# frc_operator_interface.net
KiCad netlist of a schematic drawn in EAGLE
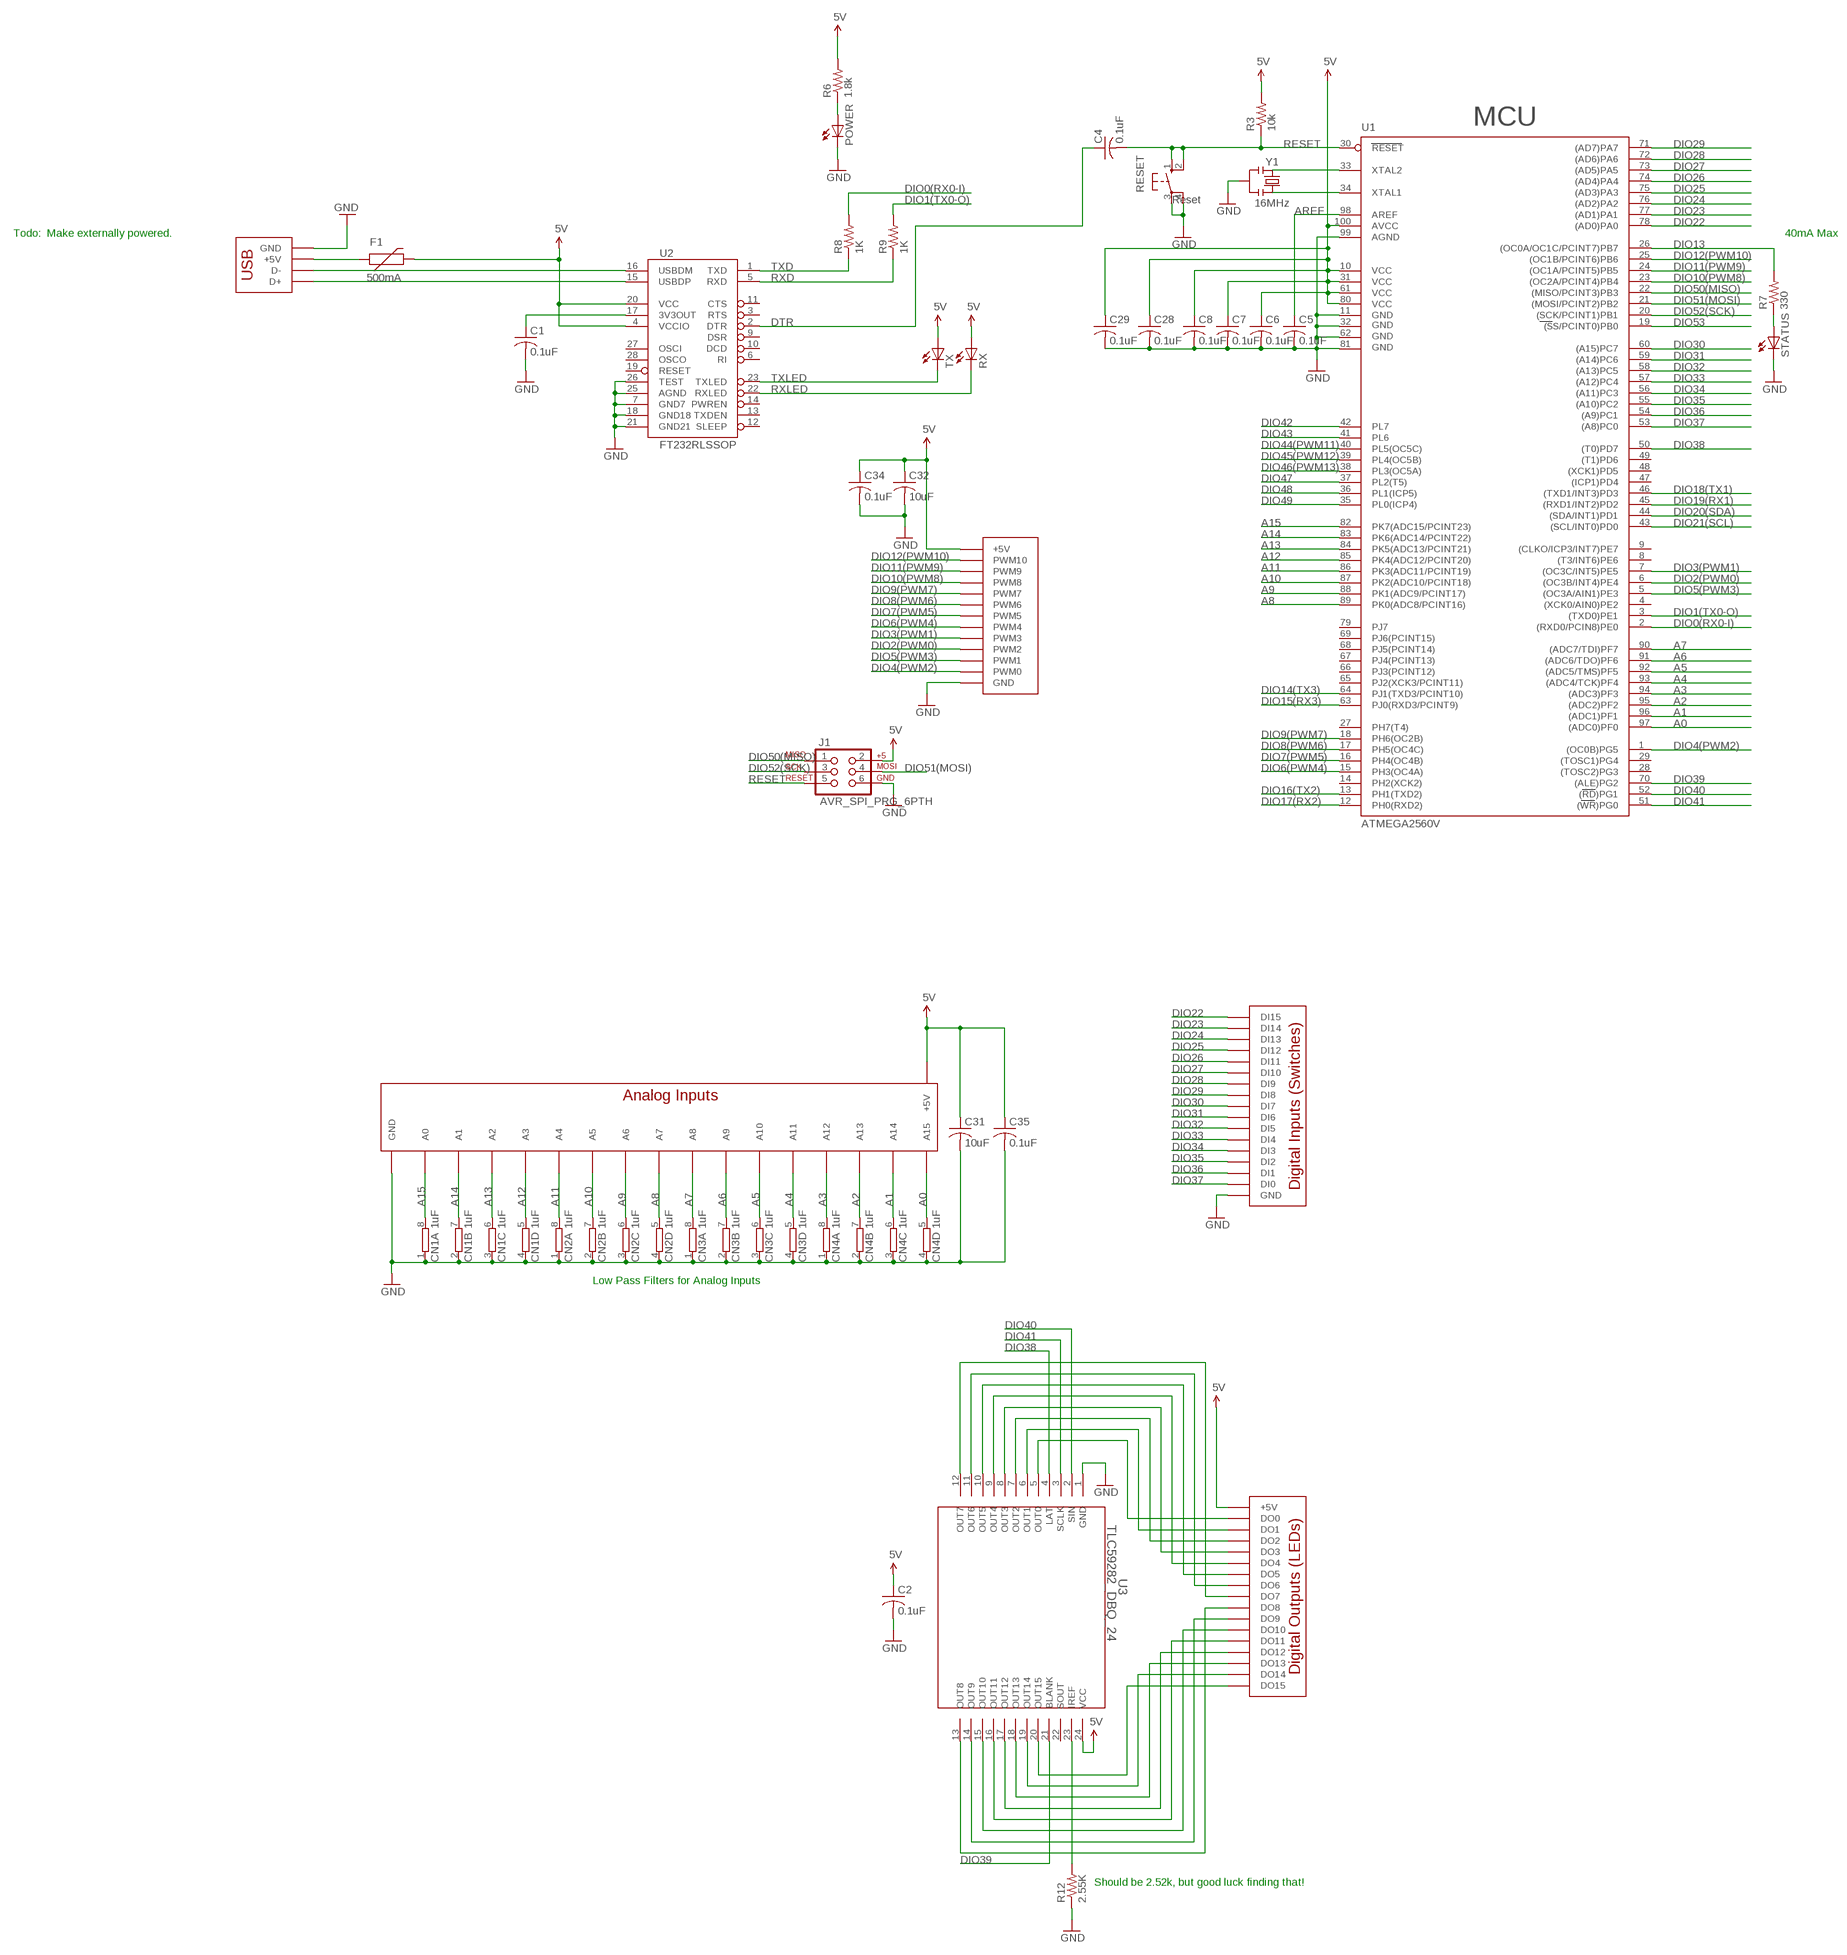
[diagram p0: schematic, sheet 1]

(export (version "E")
  (design (tool "Eeschema 10.0.6"))
  (components
    (comp (ref "C1")
      (value "0.1uF")
      (footprint "eagle-import:C1206")
      (libsource (lib "eagle-import") (part "C-USC1206"))
    )
    (comp (ref "C2")
      (value "0.1uF")
      (footprint "eagle-import:C1206")
      (libsource (lib "eagle-import") (part "C-USC1206"))
    )
    (comp (ref "C4")
      (value "0.1uF")
      (footprint "eagle-import:C1206")
      (libsource (lib "eagle-import") (part "C-USC1206"))
    )
    (comp (ref "C5")
      (value "0.1uF")
      (footprint "eagle-import:C1206")
      (libsource (lib "eagle-import") (part "C-USC1206"))
    )
    (comp (ref "C6")
      (value "0.1uF")
      (footprint "eagle-import:C1206")
      (libsource (lib "eagle-import") (part "C-USC1206"))
    )
    (comp (ref "C7")
      (value "0.1uF")
      (footprint "eagle-import:C1206")
      (libsource (lib "eagle-import") (part "C-USC1206"))
    )
    (comp (ref "C8")
      (value "0.1uF")
      (footprint "eagle-import:C1206")
      (libsource (lib "eagle-import") (part "C-USC1206"))
    )
    (comp (ref "C28")
      (value "0.1uF")
      (footprint "eagle-import:C1206")
      (libsource (lib "eagle-import") (part "C-USC1206"))
    )
    (comp (ref "C29")
      (value "0.1uF")
      (footprint "eagle-import:C1206")
      (libsource (lib "eagle-import") (part "C-USC1206"))
    )
    (comp (ref "C31")
      (value "10uF")
      (footprint "eagle-import:C1206")
      (libsource (lib "eagle-import") (part "C-USC1206"))
    )
    (comp (ref "C32")
      (value "10uF")
      (footprint "eagle-import:C1206")
      (libsource (lib "eagle-import") (part "C-USC1206"))
    )
    (comp (ref "C34")
      (value "0.1uF")
      (footprint "eagle-import:C1206")
      (libsource (lib "eagle-import") (part "C-USC1206"))
    )
    (comp (ref "C35")
      (value "0.1uF")
      (footprint "eagle-import:C1206")
      (libsource (lib "eagle-import") (part "C-USC1206"))
    )
    (comp (ref "CN1")
      (value "1uF")
      (footprint "eagle-import:EXB38V")
      (libsource (lib "eagle-import") (part "4R-NEXB38V"))
    )
    (comp (ref "CN2")
      (value "1uF")
      (footprint "eagle-import:EXB38V")
      (libsource (lib "eagle-import") (part "4R-NEXB38V"))
    )
    (comp (ref "CN3")
      (value "1uF")
      (footprint "eagle-import:EXB38V")
      (libsource (lib "eagle-import") (part "4R-NEXB38V"))
    )
    (comp (ref "CN4")
      (value "1uF")
      (footprint "eagle-import:EXB38V")
      (libsource (lib "eagle-import") (part "4R-NEXB38V"))
    )
    (comp (ref "F1")
      (value "500mA")
      (footprint "eagle-import:PTC-1206")
      (libsource (lib "eagle-import") (part "PTCSMD"))
    )
    (comp (ref "J1")
      (value "AVR_SPI_PRG_6PTH")
      (footprint "eagle-import:2X3")
      (libsource (lib "eagle-import") (part "AVR_SPI_PRG_6PTH"))
    )
    (comp (ref "J2")
      (value "ANALOGHEADER")
      (footprint "eagle-import:ANALOGHEADER")
      (libsource (lib "eagle-import") (part "ANALOGHEADER"))
    )
    (comp (ref "J3")
      (value "DIGITALIN")
      (footprint "eagle-import:DIGITALIN")
      (libsource (lib "eagle-import") (part "DIGITALIN"))
    )
    (comp (ref "J4")
      (value "DIGITALOUTPUTS")
      (footprint "eagle-import:DIGITALOUT")
      (libsource (lib "eagle-import") (part "DIGITALOUTPUTS"))
    )
    (comp (ref "J5")
      (value "PWMHEADER")
      (footprint "eagle-import:PWMHEADER")
      (libsource (lib "eagle-import") (part "PWMHEADER"))
    )
    (comp (ref "J6")
      (value "UE27BC54130-USB")
      (footprint "eagle-import:UE27BC54130-USB")
      (libsource (lib "eagle-import") (part "UE27BC54130-USB"))
    )
    (comp (ref "POWER")
      (value "LED3MM")
      (footprint "eagle-import:LED3MM")
      (libsource (lib "eagle-import") (part "LED3MM"))
    )
    (comp (ref "R3")
      (value "10k")
      (footprint "eagle-import:M1206")
      (libsource (lib "eagle-import") (part "R-US_M1206"))
    )
    (comp (ref "R6")
      (value "1.8k")
      (footprint "eagle-import:M1206")
      (libsource (lib "eagle-import") (part "R-US_M1206"))
    )
    (comp (ref "R7")
      (value "330")
      (footprint "eagle-import:M1206")
      (libsource (lib "eagle-import") (part "R-US_M1206"))
    )
    (comp (ref "R8")
      (value "1K")
      (footprint "eagle-import:M1206")
      (libsource (lib "eagle-import") (part "R-US_M1206"))
    )
    (comp (ref "R9")
      (value "1K")
      (footprint "eagle-import:M1206")
      (libsource (lib "eagle-import") (part "R-US_M1206"))
    )
    (comp (ref "R12")
      (value "2.55K")
      (footprint "eagle-import:M1206")
      (libsource (lib "eagle-import") (part "R-US_M1206"))
    )
    (comp (ref "RESET")
      (value "10-XX")
      (footprint "eagle-import:B3F-10XX")
      (fields (field (name "MPN") "B3F-1000"))
      (libsource (lib "eagle-import") (part "10-XX"))
    )
    (comp (ref "RX")
      (value "LED3MM")
      (footprint "eagle-import:LED3MM")
      (libsource (lib "eagle-import") (part "LED3MM"))
    )
    (comp (ref "STATUS")
      (value "LED3MM")
      (footprint "eagle-import:LED3MM")
      (libsource (lib "eagle-import") (part "LED3MM"))
    )
    (comp (ref "TX")
      (value "LED3MM")
      (footprint "eagle-import:LED3MM")
      (libsource (lib "eagle-import") (part "LED3MM"))
    )
    (comp (ref "U1")
      (value "ATMEGA2560AU")
      (footprint "eagle-import:TQFP100")
      (libsource (lib "eagle-import") (part "ATMEGA2560AU"))
    )
    (comp (ref "U2")
      (value "FT232RLSSOP")
      (footprint "eagle-import:SSOP28DB")
      (libsource (lib "eagle-import") (part "FT232RLSSOP"))
    )
    (comp (ref "U3")
      (value "TLC59282_DBQ_24")
      (footprint "eagle-import:DBQ24")
      (fields
        (field (name "GENERIC_PART_NUMBER") "TLC59282")
        (field (name "MANUFACTURER") "Texas Instruments")
        (field (name "MANUFACTURER_PART_NUMBER") "tlc59282_dbq_24")
      )
      (libsource (lib "eagle-import") (part "TLC59282_DBQ_24"))
    )
    (comp (ref "Y1")
      (value "RESONATORSMD")
      (footprint "eagle-import:RESONATOR-SMD")
      (libsource (lib "eagle-import") (part "RESONATORSMD"))
    )
  )
  (nets
    (net (code "1") (name "/A0") (class "Default")
      (node (ref "CN4") (pin "5") (pinfunction "2_5") (pintype "passive"))
      (node (ref "J2") (pin "15") (pinfunction "A15_15") (pintype "bidirectional"))
      (node (ref "U1") (pin "97") (pinfunction "(ADC0)PF0_97") (pintype "bidirectional"))
    )
    (net (code "2") (name "/A1") (class "Default")
      (node (ref "CN4") (pin "6") (pinfunction "2_6") (pintype "passive"))
      (node (ref "J2") (pin "14") (pinfunction "A14_14") (pintype "bidirectional"))
      (node (ref "U1") (pin "96") (pinfunction "(ADC1)PF1_96") (pintype "bidirectional"))
    )
    (net (code "3") (name "/A2") (class "Default")
      (node (ref "CN4") (pin "7") (pinfunction "2_7") (pintype "passive"))
      (node (ref "J2") (pin "13") (pinfunction "A13_13") (pintype "bidirectional"))
      (node (ref "U1") (pin "95") (pinfunction "(ADC2)PF2_95") (pintype "bidirectional"))
    )
    (net (code "4") (name "/A3") (class "Default")
      (node (ref "CN4") (pin "8") (pinfunction "2_8") (pintype "passive"))
      (node (ref "J2") (pin "12") (pinfunction "A12_12") (pintype "bidirectional"))
      (node (ref "U1") (pin "94") (pinfunction "(ADC3)PF3_94") (pintype "bidirectional"))
    )
    (net (code "5") (name "/A4") (class "Default")
      (node (ref "CN3") (pin "5") (pinfunction "2_5") (pintype "passive"))
      (node (ref "J2") (pin "11") (pinfunction "A11_11") (pintype "bidirectional"))
      (node (ref "U1") (pin "93") (pinfunction "(ADC4/TCK)PF4_93") (pintype "bidirectional"))
    )
    (net (code "6") (name "/A5") (class "Default")
      (node (ref "CN3") (pin "6") (pinfunction "2_6") (pintype "passive"))
      (node (ref "J2") (pin "10") (pinfunction "A10_10") (pintype "bidirectional"))
      (node (ref "U1") (pin "92") (pinfunction "(ADC5/TMS)PF5_92") (pintype "bidirectional"))
    )
    (net (code "7") (name "/A6") (class "Default")
      (node (ref "CN3") (pin "7") (pinfunction "2_7") (pintype "passive"))
      (node (ref "J2") (pin "9") (pinfunction "A9_9") (pintype "bidirectional"))
      (node (ref "U1") (pin "91") (pinfunction "(ADC6/TDO)PF6_91") (pintype "bidirectional"))
    )
    (net (code "8") (name "/A7") (class "Default")
      (node (ref "CN3") (pin "8") (pinfunction "2_8") (pintype "passive"))
      (node (ref "J2") (pin "8") (pinfunction "A8_8") (pintype "bidirectional"))
      (node (ref "U1") (pin "90") (pinfunction "(ADC7/TDI)PF7_90") (pintype "bidirectional"))
    )
    (net (code "9") (name "/A8") (class "Default")
      (node (ref "CN2") (pin "5") (pinfunction "2_5") (pintype "passive"))
      (node (ref "J2") (pin "7") (pinfunction "A7_7") (pintype "bidirectional"))
      (node (ref "U1") (pin "89") (pinfunction "PK0(ADC8/PCINT16)_89") (pintype "bidirectional"))
    )
    (net (code "10") (name "/A9") (class "Default")
      (node (ref "CN2") (pin "6") (pinfunction "2_6") (pintype "passive"))
      (node (ref "J2") (pin "6") (pinfunction "A6_6") (pintype "bidirectional"))
      (node (ref "U1") (pin "88") (pinfunction "PK1(ADC9/PCINT17)_88") (pintype "bidirectional"))
    )
    (net (code "11") (name "/A10") (class "Default")
      (node (ref "CN2") (pin "7") (pinfunction "2_7") (pintype "passive"))
      (node (ref "J2") (pin "5") (pinfunction "A5_5") (pintype "bidirectional"))
      (node (ref "U1") (pin "87") (pinfunction "PK2(ADC10/PCINT18)_87") (pintype "bidirectional"))
    )
    (net (code "12") (name "/A11") (class "Default")
      (node (ref "CN2") (pin "8") (pinfunction "2_8") (pintype "passive"))
      (node (ref "J2") (pin "4") (pinfunction "A4_4") (pintype "bidirectional"))
      (node (ref "U1") (pin "86") (pinfunction "PK3(ADC11/PCINT19)_86") (pintype "bidirectional"))
    )
    (net (code "13") (name "/A12") (class "Default")
      (node (ref "CN1") (pin "5") (pinfunction "2_5") (pintype "passive"))
      (node (ref "J2") (pin "3") (pinfunction "A3_3") (pintype "bidirectional"))
      (node (ref "U1") (pin "85") (pinfunction "PK4(ADC12/PCINT20)_85") (pintype "bidirectional"))
    )
    (net (code "14") (name "/A13") (class "Default")
      (node (ref "CN1") (pin "6") (pinfunction "2_6") (pintype "passive"))
      (node (ref "J2") (pin "2") (pinfunction "A2_2") (pintype "bidirectional"))
      (node (ref "U1") (pin "84") (pinfunction "PK5(ADC13/PCINT21)_84") (pintype "bidirectional"))
    )
    (net (code "15") (name "/A14") (class "Default")
      (node (ref "CN1") (pin "7") (pinfunction "2_7") (pintype "passive"))
      (node (ref "J2") (pin "1") (pinfunction "A1_1") (pintype "bidirectional"))
      (node (ref "U1") (pin "83") (pinfunction "PK6(ADC14/PCINT22)_83") (pintype "bidirectional"))
    )
    (net (code "16") (name "/A15") (class "Default")
      (node (ref "CN1") (pin "8") (pinfunction "2_8") (pintype "passive"))
      (node (ref "J2") (pin "0") (pinfunction "A0_0") (pintype "bidirectional"))
      (node (ref "U1") (pin "82") (pinfunction "PK7(ADC15/PCINT23)_82") (pintype "bidirectional"))
    )
    (net (code "17") (name "/AREF") (class "Default")
      (node (ref "C5") (pin "1") (pinfunction "1_1") (pintype "passive"))
      (node (ref "U1") (pin "98") (pinfunction "AREF_98") (pintype "bidirectional"))
    )
    (net (code "18") (name "/DIO0(RX0-I)") (class "Default")
      (node (ref "R8") (pin "2") (pinfunction "2_2") (pintype "passive"))
      (node (ref "U1") (pin "2") (pinfunction "(RXD0/PCIN8)PE0_2") (pintype "bidirectional"))
    )
    (net (code "19") (name "/DIO1(TX0-O)") (class "Default")
      (node (ref "R9") (pin "2") (pinfunction "2_2") (pintype "passive"))
      (node (ref "U1") (pin "3") (pinfunction "(TXD0)PE1_3") (pintype "bidirectional"))
    )
    (net (code "20") (name "/DIO2(PWM0)") (class "Default")
      (node (ref "J5") (pin "2") (pinfunction "PWM2_2") (pintype "output"))
      (node (ref "U1") (pin "6") (pinfunction "(OC3B/INT4)PE4_6") (pintype "bidirectional"))
    )
    (net (code "21") (name "/DIO3(PWM1)") (class "Default")
      (node (ref "J5") (pin "3") (pinfunction "PWM3_3") (pintype "output"))
      (node (ref "U1") (pin "7") (pinfunction "(OC3C/INT5)PE5_7") (pintype "bidirectional"))
    )
    (net (code "22") (name "/DIO4(PWM2)") (class "Default")
      (node (ref "J5") (pin "0") (pinfunction "PWM0_0") (pintype "output"))
      (node (ref "U1") (pin "1") (pinfunction "(OC0B)PG5_1") (pintype "bidirectional"))
    )
    (net (code "23") (name "/DIO5(PWM3)") (class "Default")
      (node (ref "J5") (pin "1") (pinfunction "PWM1_1") (pintype "output"))
      (node (ref "U1") (pin "5") (pinfunction "(OC3A/AIN1)PE3_5") (pintype "bidirectional"))
    )
    (net (code "24") (name "/DIO6(PWM4)") (class "Default")
      (node (ref "J5") (pin "4") (pinfunction "PWM4_4") (pintype "output"))
      (node (ref "U1") (pin "15") (pinfunction "PH3(OC4A)_15") (pintype "bidirectional"))
    )
    (net (code "25") (name "/DIO7(PWM5)") (class "Default")
      (node (ref "J5") (pin "5") (pinfunction "PWM5_5") (pintype "output"))
      (node (ref "U1") (pin "16") (pinfunction "PH4(OC4B)_16") (pintype "bidirectional"))
    )
    (net (code "26") (name "/DIO8(PWM6)") (class "Default")
      (node (ref "J5") (pin "6") (pinfunction "PWM6_6") (pintype "output"))
      (node (ref "U1") (pin "17") (pinfunction "PH5(OC4C)_17") (pintype "bidirectional"))
    )
    (net (code "27") (name "/DIO9(PWM7)") (class "Default")
      (node (ref "J5") (pin "7") (pinfunction "PWM7_7") (pintype "output"))
      (node (ref "U1") (pin "18") (pinfunction "PH6(OC2B)_18") (pintype "bidirectional"))
    )
    (net (code "28") (name "/DIO10(PWM8)") (class "Default")
      (node (ref "J5") (pin "8") (pinfunction "PWM8_8") (pintype "output"))
      (node (ref "U1") (pin "23") (pinfunction "(OC2A/PCINT4)PB4_23") (pintype "bidirectional"))
    )
    (net (code "29") (name "/DIO11(PWM9)") (class "Default")
      (node (ref "J5") (pin "9") (pinfunction "PWM9_9") (pintype "output"))
      (node (ref "U1") (pin "24") (pinfunction "(OC1A/PCINT5)PB5_24") (pintype "bidirectional"))
    )
    (net (code "30") (name "/DIO12(PWM10)") (class "Default")
      (node (ref "J5") (pin "10") (pinfunction "PWM10_10") (pintype "output"))
      (node (ref "U1") (pin "25") (pinfunction "(OC1B/PCINT6)PB6_25") (pintype "bidirectional"))
    )
    (net (code "31") (name "/DIO13") (class "Default")
      (node (ref "R7") (pin "2") (pinfunction "2_2") (pintype "passive"))
      (node (ref "U1") (pin "26") (pinfunction "(OC0A/OC1C/PCINT7)PB7_26") (pintype "bidirectional"))
    )
    (net (code "32") (name "/DIO14(TX3)") (class "Default")
      (node (ref "U1") (pin "64") (pinfunction "PJ1(TXD3/PCINT10)_64") (pintype "bidirectional"))
    )
    (net (code "33") (name "/DIO15(RX3)") (class "Default")
      (node (ref "U1") (pin "63") (pinfunction "PJ0(RXD3/PCINT9)_63") (pintype "bidirectional"))
    )
    (net (code "34") (name "/DIO16(TX2)") (class "Default")
      (node (ref "U1") (pin "13") (pinfunction "PH1(TXD2)_13") (pintype "bidirectional"))
    )
    (net (code "35") (name "/DIO17(RX2)") (class "Default")
      (node (ref "U1") (pin "12") (pinfunction "PH0(RXD2)_12") (pintype "bidirectional"))
    )
    (net (code "36") (name "/DIO18(TX1)") (class "Default")
      (node (ref "U1") (pin "46") (pinfunction "(TXD1/INT3)PD3_46") (pintype "bidirectional"))
    )
    (net (code "37") (name "/DIO19(RX1)") (class "Default")
      (node (ref "U1") (pin "45") (pinfunction "(RXD1/INT2)PD2_45") (pintype "bidirectional"))
    )
    (net (code "38") (name "/DIO20(SDA)") (class "Default")
      (node (ref "U1") (pin "44") (pinfunction "(SDA/INT1)PD1_44") (pintype "bidirectional"))
    )
    (net (code "39") (name "/DIO21(SCL)") (class "Default")
      (node (ref "U1") (pin "43") (pinfunction "(SCL/INT0)PD0_43") (pintype "bidirectional"))
    )
    (net (code "40") (name "/DIO22") (class "Default")
      (node (ref "J3") (pin "DI15") (pinfunction "DI15_DI15") (pintype "bidirectional"))
      (node (ref "U1") (pin "78") (pinfunction "(AD0)PA0_78") (pintype "bidirectional"))
    )
    (net (code "41") (name "/DIO23") (class "Default")
      (node (ref "J3") (pin "DI14") (pinfunction "DI14_DI14") (pintype "bidirectional"))
      (node (ref "U1") (pin "77") (pinfunction "(AD1)PA1_77") (pintype "bidirectional"))
    )
    (net (code "42") (name "/DIO24") (class "Default")
      (node (ref "J3") (pin "DI13") (pinfunction "DI13_DI13") (pintype "bidirectional"))
      (node (ref "U1") (pin "76") (pinfunction "(AD2)PA2_76") (pintype "bidirectional"))
    )
    (net (code "43") (name "/DIO25") (class "Default")
      (node (ref "J3") (pin "DI12") (pinfunction "DI12_DI12") (pintype "bidirectional"))
      (node (ref "U1") (pin "75") (pinfunction "(AD3)PA3_75") (pintype "bidirectional"))
    )
    (net (code "44") (name "/DIO26") (class "Default")
      (node (ref "J3") (pin "DI11") (pinfunction "DI11_DI11") (pintype "bidirectional"))
      (node (ref "U1") (pin "74") (pinfunction "(AD4)PA4_74") (pintype "bidirectional"))
    )
    (net (code "45") (name "/DIO27") (class "Default")
      (node (ref "J3") (pin "DI10") (pinfunction "DI10_DI10") (pintype "bidirectional"))
      (node (ref "U1") (pin "73") (pinfunction "(AD5)PA5_73") (pintype "bidirectional"))
    )
    (net (code "46") (name "/DIO28") (class "Default")
      (node (ref "J3") (pin "DI9") (pinfunction "DI9_DI9") (pintype "bidirectional"))
      (node (ref "U1") (pin "72") (pinfunction "(AD6)PA6_72") (pintype "bidirectional"))
    )
    (net (code "47") (name "/DIO29") (class "Default")
      (node (ref "J3") (pin "DI8") (pinfunction "DI8_DI8") (pintype "bidirectional"))
      (node (ref "U1") (pin "71") (pinfunction "(AD7)PA7_71") (pintype "bidirectional"))
    )
    (net (code "48") (name "/DIO30") (class "Default")
      (node (ref "J3") (pin "DI7") (pinfunction "DI7_DI7") (pintype "bidirectional"))
      (node (ref "U1") (pin "60") (pinfunction "(A15)PC7_60") (pintype "bidirectional"))
    )
    (net (code "49") (name "/DIO31") (class "Default")
      (node (ref "J3") (pin "DI6") (pinfunction "DI6_DI6") (pintype "bidirectional"))
      (node (ref "U1") (pin "59") (pinfunction "(A14)PC6_59") (pintype "bidirectional"))
    )
    (net (code "50") (name "/DIO32") (class "Default")
      (node (ref "J3") (pin "DI5") (pinfunction "DI5_DI5") (pintype "bidirectional"))
      (node (ref "U1") (pin "58") (pinfunction "(A13)PC5_58") (pintype "bidirectional"))
    )
    (net (code "51") (name "/DIO33") (class "Default")
      (node (ref "J3") (pin "DI4") (pinfunction "DI4_DI4") (pintype "bidirectional"))
      (node (ref "U1") (pin "57") (pinfunction "(A12)PC4_57") (pintype "bidirectional"))
    )
    (net (code "52") (name "/DIO34") (class "Default")
      (node (ref "J3") (pin "DI3") (pinfunction "DI3_DI3") (pintype "bidirectional"))
      (node (ref "U1") (pin "56") (pinfunction "(A11)PC3_56") (pintype "bidirectional"))
    )
    (net (code "53") (name "/DIO35") (class "Default")
      (node (ref "J3") (pin "DI2") (pinfunction "DI2_DI2") (pintype "bidirectional"))
      (node (ref "U1") (pin "55") (pinfunction "(A10)PC2_55") (pintype "bidirectional"))
    )
    (net (code "54") (name "/DIO36") (class "Default")
      (node (ref "J3") (pin "DI1") (pinfunction "DI1_DI1") (pintype "bidirectional"))
      (node (ref "U1") (pin "54") (pinfunction "(A9)PC1_54") (pintype "bidirectional"))
    )
    (net (code "55") (name "/DIO37") (class "Default")
      (node (ref "J3") (pin "DI0") (pinfunction "DI0_DI0") (pintype "bidirectional"))
      (node (ref "U1") (pin "53") (pinfunction "(A8)PC0_53") (pintype "bidirectional"))
    )
    (net (code "56") (name "/DIO38") (class "Default")
      (node (ref "U1") (pin "50") (pinfunction "(T0)PD7_50") (pintype "bidirectional"))
      (node (ref "U3") (pin "4") (pinfunction "LAT_4") (pintype "input"))
    )
    (net (code "57") (name "/DIO39") (class "Default")
      (node (ref "U1") (pin "70") (pinfunction "(ALE)PG2_70") (pintype "bidirectional"))
      (node (ref "U3") (pin "21") (pinfunction "BLANK_21") (pintype "input"))
    )
    (net (code "58") (name "/DIO40") (class "Default")
      (node (ref "U1") (pin "52") (pinfunction "(RD)PG1_52") (pintype "bidirectional"))
      (node (ref "U3") (pin "2") (pinfunction "SIN_2") (pintype "input"))
    )
    (net (code "59") (name "/DIO41") (class "Default")
      (node (ref "U1") (pin "51") (pinfunction "(WR)PG0_51") (pintype "bidirectional"))
      (node (ref "U3") (pin "3") (pinfunction "SCLK_3") (pintype "input"))
    )
    (net (code "60") (name "/DIO42") (class "Default")
      (node (ref "U1") (pin "42") (pinfunction "PL7_42") (pintype "bidirectional"))
    )
    (net (code "61") (name "/DIO43") (class "Default")
      (node (ref "U1") (pin "41") (pinfunction "PL6_41") (pintype "bidirectional"))
    )
    (net (code "62") (name "/DIO44(PWM11)") (class "Default")
      (node (ref "U1") (pin "40") (pinfunction "PL5(OC5C)_40") (pintype "bidirectional"))
    )
    (net (code "63") (name "/DIO45(PWM12)") (class "Default")
      (node (ref "U1") (pin "39") (pinfunction "PL4(OC5B)_39") (pintype "bidirectional"))
    )
    (net (code "64") (name "/DIO46(PWM13)") (class "Default")
      (node (ref "U1") (pin "38") (pinfunction "PL3(OC5A)_38") (pintype "bidirectional"))
    )
    (net (code "65") (name "/DIO47") (class "Default")
      (node (ref "U1") (pin "37") (pinfunction "PL2(T5)_37") (pintype "bidirectional"))
    )
    (net (code "66") (name "/DIO48") (class "Default")
      (node (ref "U1") (pin "36") (pinfunction "PL1(ICP5)_36") (pintype "bidirectional"))
    )
    (net (code "67") (name "/DIO49") (class "Default")
      (node (ref "U1") (pin "35") (pinfunction "PL0(ICP4)_35") (pintype "bidirectional"))
    )
    (net (code "68") (name "/DIO50(MISO)") (class "Default")
      (node (ref "J1") (pin "1") (pinfunction "1_1") (pintype "passive"))
      (node (ref "U1") (pin "22") (pinfunction "(MISO/PCINT3)PB3_22") (pintype "bidirectional"))
    )
    (net (code "69") (name "/DIO51(MOSI)") (class "Default")
      (node (ref "J1") (pin "4") (pinfunction "4_4") (pintype "passive"))
      (node (ref "U1") (pin "21") (pinfunction "(MOSI/PCINT2)PB2_21") (pintype "bidirectional"))
    )
    (net (code "70") (name "/DIO52(SCK)") (class "Default")
      (node (ref "J1") (pin "3") (pinfunction "3_3") (pintype "passive"))
      (node (ref "U1") (pin "20") (pinfunction "(SCK/PCINT1)PB1_20") (pintype "bidirectional"))
    )
    (net (code "71") (name "/DIO53") (class "Default")
      (node (ref "U1") (pin "19") (pinfunction "(SS/PCINT0)PB0_19") (pintype "bidirectional"))
    )
    (net (code "72") (name "/DTR") (class "Default")
      (node (ref "C4") (pin "1") (pinfunction "1_1") (pintype "passive"))
      (node (ref "U2") (pin "2") (pinfunction "DTR_2") (pintype "output"))
    )
    (net (code "73") (name "/RESET") (class "Default")
      (node (ref "C4") (pin "2") (pinfunction "2_2") (pintype "passive"))
      (node (ref "J1") (pin "5") (pinfunction "5_5") (pintype "passive"))
      (node (ref "R3") (pin "1") (pinfunction "1_1") (pintype "passive"))
      (node (ref "RESET") (pin "1") (pinfunction "S_1") (pintype "passive"))
      (node (ref "RESET") (pin "2") (pinfunction "S1_2") (pintype "passive"))
      (node (ref "U1") (pin "30") (pinfunction "RESET_30") (pintype "input"))
    )
    (net (code "74") (name "/RXD") (class "Default")
      (node (ref "R9") (pin "1") (pinfunction "1_1") (pintype "passive"))
      (node (ref "U2") (pin "5") (pinfunction "RXD_5") (pintype "input"))
    )
    (net (code "75") (name "/RXLED") (class "Default")
      (node (ref "RX") (pin "K") (pinfunction "C_K") (pintype "passive"))
      (node (ref "U2") (pin "22") (pinfunction "RXLED_22") (pintype "input"))
    )
    (net (code "76") (name "/TXD") (class "Default")
      (node (ref "R8") (pin "1") (pinfunction "1_1") (pintype "passive"))
      (node (ref "U2") (pin "1") (pinfunction "TXD_1") (pintype "output"))
    )
    (net (code "77") (name "/TXLED") (class "Default")
      (node (ref "TX") (pin "K") (pinfunction "C_K") (pintype "passive"))
      (node (ref "U2") (pin "23") (pinfunction "TXLED_23") (pintype "input"))
    )
    (net (code "78") (name "5V") (class "Default")
      (node (ref "C2") (pin "1") (pinfunction "1_1") (pintype "passive"))
      (node (ref "C28") (pin "1") (pinfunction "1_1") (pintype "passive"))
      (node (ref "C29") (pin "1") (pinfunction "1_1") (pintype "passive"))
      (node (ref "C31") (pin "1") (pinfunction "1_1") (pintype "passive"))
      (node (ref "C32") (pin "1") (pinfunction "1_1") (pintype "passive"))
      (node (ref "C34") (pin "1") (pinfunction "1_1") (pintype "passive"))
      (node (ref "C35") (pin "1") (pinfunction "1_1") (pintype "passive"))
      (node (ref "C6") (pin "1") (pinfunction "1_1") (pintype "passive"))
      (node (ref "C7") (pin "1") (pinfunction "1_1") (pintype "passive"))
      (node (ref "C8") (pin "1") (pinfunction "1_1") (pintype "passive"))
      (node (ref "F1") (pin "2") (pinfunction "2_2") (pintype "bidirectional"))
      (node (ref "J1") (pin "2") (pinfunction "2_2") (pintype "passive"))
      (node (ref "J2") (pin "+5V@0") (pinfunction "+5V_+5V@0") (pintype "bidirectional"))
      (node (ref "J2") (pin "+5V@1") (pinfunction "+5V_+5V@1") (pintype "bidirectional"))
      (node (ref "J2") (pin "+5V@10") (pinfunction "+5V_+5V@10") (pintype "bidirectional"))
      (node (ref "J2") (pin "+5V@11") (pinfunction "+5V_+5V@11") (pintype "bidirectional"))
      (node (ref "J2") (pin "+5V@12") (pinfunction "+5V_+5V@12") (pintype "bidirectional"))
      (node (ref "J2") (pin "+5V@13") (pinfunction "+5V_+5V@13") (pintype "bidirectional"))
      (node (ref "J2") (pin "+5V@14") (pinfunction "+5V_+5V@14") (pintype "bidirectional"))
      (node (ref "J2") (pin "+5V@15") (pinfunction "+5V_+5V@15") (pintype "bidirectional"))
      (node (ref "J2") (pin "+5V@2") (pinfunction "+5V_+5V@2") (pintype "bidirectional"))
      (node (ref "J2") (pin "+5V@3") (pinfunction "+5V_+5V@3") (pintype "bidirectional"))
      (node (ref "J2") (pin "+5V@4") (pinfunction "+5V_+5V@4") (pintype "bidirectional"))
      (node (ref "J2") (pin "+5V@5") (pinfunction "+5V_+5V@5") (pintype "bidirectional"))
      (node (ref "J2") (pin "+5V@6") (pinfunction "+5V_+5V@6") (pintype "bidirectional"))
      (node (ref "J2") (pin "+5V@7") (pinfunction "+5V_+5V@7") (pintype "bidirectional"))
      (node (ref "J2") (pin "+5V@8") (pinfunction "+5V_+5V@8") (pintype "bidirectional"))
      (node (ref "J2") (pin "+5V@9") (pinfunction "+5V_+5V@9") (pintype "bidirectional"))
      (node (ref "J4") (pin "+5V@0") (pinfunction "+5V_+5V@0") (pintype "power_in"))
      (node (ref "J4") (pin "+5V@1") (pinfunction "+5V_+5V@1") (pintype "power_in"))
      (node (ref "J4") (pin "+5V@10") (pinfunction "+5V_+5V@10") (pintype "power_in"))
      (node (ref "J4") (pin "+5V@11") (pinfunction "+5V_+5V@11") (pintype "power_in"))
      (node (ref "J4") (pin "+5V@12") (pinfunction "+5V_+5V@12") (pintype "power_in"))
      (node (ref "J4") (pin "+5V@13") (pinfunction "+5V_+5V@13") (pintype "power_in"))
      (node (ref "J4") (pin "+5V@14") (pinfunction "+5V_+5V@14") (pintype "power_in"))
      (node (ref "J4") (pin "+5V@15") (pinfunction "+5V_+5V@15") (pintype "power_in"))
      (node (ref "J4") (pin "+5V@2") (pinfunction "+5V_+5V@2") (pintype "power_in"))
      (node (ref "J4") (pin "+5V@3") (pinfunction "+5V_+5V@3") (pintype "power_in"))
      (node (ref "J4") (pin "+5V@4") (pinfunction "+5V_+5V@4") (pintype "power_in"))
      (node (ref "J4") (pin "+5V@5") (pinfunction "+5V_+5V@5") (pintype "power_in"))
      (node (ref "J4") (pin "+5V@6") (pinfunction "+5V_+5V@6") (pintype "power_in"))
      (node (ref "J4") (pin "+5V@7") (pinfunction "+5V_+5V@7") (pintype "power_in"))
      (node (ref "J4") (pin "+5V@8") (pinfunction "+5V_+5V@8") (pintype "power_in"))
      (node (ref "J4") (pin "+5V@9") (pinfunction "+5V_+5V@9") (pintype "power_in"))
      (node (ref "J5") (pin "+5V@10") (pinfunction "+5V_+5V@10") (pintype "power_in"))
      (node (ref "J5") (pin "+5V@11") (pinfunction "+5V_+5V@11") (pintype "power_in"))
      (node (ref "J5") (pin "+5V@12") (pinfunction "+5V_+5V@12") (pintype "power_in"))
      (node (ref "J5") (pin "+5V@13") (pinfunction "+5V_+5V@13") (pintype "power_in"))
      (node (ref "J5") (pin "+5V@3") (pinfunction "+5V_+5V@3") (pintype "power_in"))
      (node (ref "J5") (pin "+5V@4") (pinfunction "+5V_+5V@4") (pintype "power_in"))
      (node (ref "J5") (pin "+5V@5") (pinfunction "+5V_+5V@5") (pintype "power_in"))
      (node (ref "J5") (pin "+5V@6") (pinfunction "+5V_+5V@6") (pintype "power_in"))
      (node (ref "J5") (pin "+5V@7") (pinfunction "+5V_+5V@7") (pintype "power_in"))
      (node (ref "J5") (pin "+5V@8") (pinfunction "+5V_+5V@8") (pintype "power_in"))
      (node (ref "J5") (pin "+5V@9") (pinfunction "+5V_+5V@9") (pintype "power_in"))
      (node (ref "R3") (pin "2") (pinfunction "2_2") (pintype "passive"))
      (node (ref "R6") (pin "2") (pinfunction "2_2") (pintype "passive"))
      (node (ref "RX") (pin "A") (pinfunction "A_A") (pintype "passive"))
      (node (ref "TX") (pin "A") (pinfunction "A_A") (pintype "passive"))
      (node (ref "U1") (pin "10") (pinfunction "VCC_10") (pintype "power_in"))
      (node (ref "U1") (pin "100") (pinfunction "AVCC_100") (pintype "power_in"))
      (node (ref "U1") (pin "31") (pinfunction "VCC1_31") (pintype "power_in"))
      (node (ref "U1") (pin "61") (pinfunction "VCC2_61") (pintype "power_in"))
      (node (ref "U1") (pin "80") (pinfunction "VCC3_80") (pintype "power_in"))
      (node (ref "U2") (pin "20") (pinfunction "VCC_20") (pintype "power_in"))
      (node (ref "U2") (pin "4") (pinfunction "VCCIO_4") (pintype "power_in"))
      (node (ref "U3") (pin "24") (pinfunction "VCC_24") (pintype "power_in"))
    )
    (net (code "79") (name "GND") (class "Default")
      (node (ref "C1") (pin "2") (pinfunction "2_2") (pintype "passive"))
      (node (ref "C2") (pin "2") (pinfunction "2_2") (pintype "passive"))
      (node (ref "C28") (pin "2") (pinfunction "2_2") (pintype "passive"))
      (node (ref "C29") (pin "2") (pinfunction "2_2") (pintype "passive"))
      (node (ref "C31") (pin "2") (pinfunction "2_2") (pintype "passive"))
      (node (ref "C32") (pin "2") (pinfunction "2_2") (pintype "passive"))
      (node (ref "C34") (pin "2") (pinfunction "2_2") (pintype "passive"))
      (node (ref "C35") (pin "2") (pinfunction "2_2") (pintype "passive"))
      (node (ref "C5") (pin "2") (pinfunction "2_2") (pintype "passive"))
      (node (ref "C6") (pin "2") (pinfunction "2_2") (pintype "passive"))
      (node (ref "C7") (pin "2") (pinfunction "2_2") (pintype "passive"))
      (node (ref "C8") (pin "2") (pinfunction "2_2") (pintype "passive"))
      (node (ref "CN1") (pin "1") (pinfunction "1_1") (pintype "passive"))
      (node (ref "CN1") (pin "2") (pinfunction "1_2") (pintype "passive"))
      (node (ref "CN1") (pin "3") (pinfunction "1_3") (pintype "passive"))
      (node (ref "CN1") (pin "4") (pinfunction "1_4") (pintype "passive"))
      (node (ref "CN2") (pin "1") (pinfunction "1_1") (pintype "passive"))
      (node (ref "CN2") (pin "2") (pinfunction "1_2") (pintype "passive"))
      (node (ref "CN2") (pin "3") (pinfunction "1_3") (pintype "passive"))
      (node (ref "CN2") (pin "4") (pinfunction "1_4") (pintype "passive"))
      (node (ref "CN3") (pin "1") (pinfunction "1_1") (pintype "passive"))
      (node (ref "CN3") (pin "2") (pinfunction "1_2") (pintype "passive"))
      (node (ref "CN3") (pin "3") (pinfunction "1_3") (pintype "passive"))
      (node (ref "CN3") (pin "4") (pinfunction "1_4") (pintype "passive"))
      (node (ref "CN4") (pin "1") (pinfunction "1_1") (pintype "passive"))
      (node (ref "CN4") (pin "2") (pinfunction "1_2") (pintype "passive"))
      (node (ref "CN4") (pin "3") (pinfunction "1_3") (pintype "passive"))
      (node (ref "CN4") (pin "4") (pinfunction "1_4") (pintype "passive"))
      (node (ref "J1") (pin "6") (pinfunction "6_6") (pintype "passive"))
      (node (ref "J2") (pin "GND@0") (pinfunction "GND_GND@0") (pintype "bidirectional"))
      (node (ref "J2") (pin "GND@1") (pinfunction "GND_GND@1") (pintype "bidirectional"))
      (node (ref "J2") (pin "GND@10") (pinfunction "GND_GND@10") (pintype "bidirectional"))
      (node (ref "J2") (pin "GND@11") (pinfunction "GND_GND@11") (pintype "bidirectional"))
      (node (ref "J2") (pin "GND@12") (pinfunction "GND_GND@12") (pintype "bidirectional"))
      (node (ref "J2") (pin "GND@13") (pinfunction "GND_GND@13") (pintype "bidirectional"))
      (node (ref "J2") (pin "GND@14") (pinfunction "GND_GND@14") (pintype "bidirectional"))
      (node (ref "J2") (pin "GND@15") (pinfunction "GND_GND@15") (pintype "bidirectional"))
      (node (ref "J2") (pin "GND@2") (pinfunction "GND_GND@2") (pintype "bidirectional"))
      (node (ref "J2") (pin "GND@3") (pinfunction "GND_GND@3") (pintype "bidirectional"))
      (node (ref "J2") (pin "GND@4") (pinfunction "GND_GND@4") (pintype "bidirectional"))
      (node (ref "J2") (pin "GND@5") (pinfunction "GND_GND@5") (pintype "bidirectional"))
      (node (ref "J2") (pin "GND@6") (pinfunction "GND_GND@6") (pintype "bidirectional"))
      (node (ref "J2") (pin "GND@7") (pinfunction "GND_GND@7") (pintype "bidirectional"))
      (node (ref "J2") (pin "GND@8") (pinfunction "GND_GND@8") (pintype "bidirectional"))
      (node (ref "J2") (pin "GND@9") (pinfunction "GND_GND@9") (pintype "bidirectional"))
      (node (ref "J3") (pin "GND@0") (pinfunction "GND_GND@0") (pintype "power_in"))
      (node (ref "J3") (pin "GND@1") (pinfunction "GND_GND@1") (pintype "power_in"))
      (node (ref "J3") (pin "GND@10") (pinfunction "GND_GND@10") (pintype "power_in"))
      (node (ref "J3") (pin "GND@11") (pinfunction "GND_GND@11") (pintype "power_in"))
      (node (ref "J3") (pin "GND@12") (pinfunction "GND_GND@12") (pintype "power_in"))
      (node (ref "J3") (pin "GND@13") (pinfunction "GND_GND@13") (pintype "power_in"))
      (node (ref "J3") (pin "GND@14") (pinfunction "GND_GND@14") (pintype "power_in"))
      (node (ref "J3") (pin "GND@15") (pinfunction "GND_GND@15") (pintype "power_in"))
      (node (ref "J3") (pin "GND@2") (pinfunction "GND_GND@2") (pintype "power_in"))
      (node (ref "J3") (pin "GND@3") (pinfunction "GND_GND@3") (pintype "power_in"))
      (node (ref "J3") (pin "GND@4") (pinfunction "GND_GND@4") (pintype "power_in"))
      (node (ref "J3") (pin "GND@5") (pinfunction "GND_GND@5") (pintype "power_in"))
      (node (ref "J3") (pin "GND@6") (pinfunction "GND_GND@6") (pintype "power_in"))
      (node (ref "J3") (pin "GND@7") (pinfunction "GND_GND@7") (pintype "power_in"))
      (node (ref "J3") (pin "GND@8") (pinfunction "GND_GND@8") (pintype "power_in"))
      (node (ref "J3") (pin "GND@9") (pinfunction "GND_GND@9") (pintype "power_in"))
      (node (ref "J5") (pin "GND@10") (pinfunction "GND_GND@10") (pintype "power_in"))
      (node (ref "J5") (pin "GND@11") (pinfunction "GND_GND@11") (pintype "power_in"))
      (node (ref "J5") (pin "GND@12") (pinfunction "GND_GND@12") (pintype "power_in"))
      (node (ref "J5") (pin "GND@13") (pinfunction "GND_GND@13") (pintype "power_in"))
      (node (ref "J5") (pin "GND@3") (pinfunction "GND_GND@3") (pintype "power_in"))
      (node (ref "J5") (pin "GND@4") (pinfunction "GND_GND@4") (pintype "power_in"))
      (node (ref "J5") (pin "GND@5") (pinfunction "GND_GND@5") (pintype "power_in"))
      (node (ref "J5") (pin "GND@6") (pinfunction "GND_GND@6") (pintype "power_in"))
      (node (ref "J5") (pin "GND@7") (pinfunction "GND_GND@7") (pintype "power_in"))
      (node (ref "J5") (pin "GND@8") (pinfunction "GND_GND@8") (pintype "power_in"))
      (node (ref "J5") (pin "GND@9") (pinfunction "GND_GND@9") (pintype "power_in"))
      (node (ref "J6") (pin "GND@0") (pinfunction "GND_GND@0") (pintype "power_in"))
      (node (ref "J6") (pin "GND@1") (pinfunction "GND_GND@1") (pintype "power_in"))
      (node (ref "J6") (pin "GND@2") (pinfunction "GND_GND@2") (pintype "power_in"))
      (node (ref "POWER") (pin "K") (pinfunction "C_K") (pintype "passive"))
      (node (ref "R12") (pin "1") (pinfunction "1_1") (pintype "passive"))
      (node (ref "RESET") (pin "3") (pinfunction "P_3") (pintype "passive"))
      (node (ref "RESET") (pin "4") (pinfunction "P1_4") (pintype "passive"))
      (node (ref "STATUS") (pin "K") (pinfunction "C_K") (pintype "passive"))
      (node (ref "U1") (pin "11") (pinfunction "GND_11") (pintype "power_in"))
      (node (ref "U1") (pin "32") (pinfunction "GND1_32") (pintype "power_in"))
      (node (ref "U1") (pin "62") (pinfunction "GND2_62") (pintype "power_in"))
      (node (ref "U1") (pin "81") (pinfunction "GND3_81") (pintype "power_in"))
      (node (ref "U1") (pin "99") (pinfunction "AGND_99") (pintype "power_in"))
      (node (ref "U2") (pin "18") (pinfunction "GND18_18") (pintype "power_in"))
      (node (ref "U2") (pin "21") (pinfunction "GND21_21") (pintype "power_in"))
      (node (ref "U2") (pin "25") (pinfunction "AGND_25") (pintype "power_in"))
      (node (ref "U2") (pin "26") (pinfunction "TEST_26") (pintype "input"))
      (node (ref "U2") (pin "7") (pinfunction "GND7_7") (pintype "power_in"))
      (node (ref "U3") (pin "1") (pinfunction "GND_1") (pintype "power_in"))
      (node (ref "Y1") (pin "2") (pinfunction "2_2") (pintype "passive"))
    )
    (net (code "80") (name "Net-(F1-Pad1)") (class "Default")
      (node (ref "F1") (pin "1") (pinfunction "1_1") (pintype "bidirectional"))
      (node (ref "J6") (pin "+5V") (pinfunction "+5V_+5V") (pintype "power_in"))
    )
    (net (code "81") (name "Net-(J6-D+)") (class "Default")
      (node (ref "J6") (pin "+DATA") (pinfunction "D+_+DATA") (pintype "bidirectional"))
      (node (ref "U2") (pin "15") (pinfunction "USBDP_15") (pintype "bidirectional"))
    )
    (net (code "82") (name "Net-(J6-D-)") (class "Default")
      (node (ref "J6") (pin "-DATA") (pinfunction "D-_-DATA") (pintype "bidirectional"))
      (node (ref "U2") (pin "16") (pinfunction "USBDM_16") (pintype "bidirectional"))
    )
    (net (code "83") (name "Net-(POWER-PadA)") (class "Default")
      (node (ref "POWER") (pin "A") (pinfunction "A_A") (pintype "passive"))
      (node (ref "R6") (pin "1") (pinfunction "1_1") (pintype "passive"))
    )
    (net (code "84") (name "Net-(R7-Pad1)") (class "Default")
      (node (ref "R7") (pin "1") (pinfunction "1_1") (pintype "passive"))
      (node (ref "STATUS") (pin "A") (pinfunction "A_A") (pintype "passive"))
    )
    (net (code "85") (name "Net-(U1-XTAL1)") (class "Default")
      (node (ref "U1") (pin "34") (pinfunction "XTAL1_34") (pintype "input"))
      (node (ref "Y1") (pin "3") (pinfunction "3_3") (pintype "passive"))
    )
    (net (code "86") (name "Net-(U1-XTAL2)") (class "Default")
      (node (ref "U1") (pin "33") (pinfunction "XTAL2_33") (pintype "output"))
      (node (ref "Y1") (pin "1") (pinfunction "1_1") (pintype "passive"))
    )
    (net (code "87") (name "Net-(U2-3V3OUT)") (class "Default")
      (node (ref "C1") (pin "1") (pinfunction "1_1") (pintype "passive"))
      (node (ref "U2") (pin "17") (pinfunction "3V3OUT_17") (pintype "output"))
    )
    (net (code "88") (name "Net-(U3-IREF)") (class "Default")
      (node (ref "R12") (pin "2") (pinfunction "2_2") (pintype "passive"))
      (node (ref "U3") (pin "23") (pinfunction "IREF_23") (pintype "bidirectional"))
    )
    (net (code "89") (name "Net-(U3-OUT0)") (class "Default")
      (node (ref "J4") (pin "DO0") (pinfunction "DO0_DO0") (pintype "bidirectional"))
      (node (ref "U3") (pin "5") (pinfunction "OUT0_5") (pintype "output"))
    )
    (net (code "90") (name "Net-(U3-OUT1)") (class "Default")
      (node (ref "J4") (pin "DO1") (pinfunction "DO1_DO1") (pintype "bidirectional"))
      (node (ref "U3") (pin "6") (pinfunction "OUT1_6") (pintype "output"))
    )
    (net (code "91") (name "Net-(U3-OUT2)") (class "Default")
      (node (ref "J4") (pin "DO2") (pinfunction "DO2_DO2") (pintype "bidirectional"))
      (node (ref "U3") (pin "7") (pinfunction "OUT2_7") (pintype "output"))
    )
    (net (code "92") (name "Net-(U3-OUT3)") (class "Default")
      (node (ref "J4") (pin "DO3") (pinfunction "DO3_DO3") (pintype "bidirectional"))
      (node (ref "U3") (pin "8") (pinfunction "OUT3_8") (pintype "output"))
    )
    (net (code "93") (name "Net-(U3-OUT4)") (class "Default")
      (node (ref "J4") (pin "DO4") (pinfunction "DO4_DO4") (pintype "bidirectional"))
      (node (ref "U3") (pin "9") (pinfunction "OUT4_9") (pintype "output"))
    )
    (net (code "94") (name "Net-(U3-OUT5)") (class "Default")
      (node (ref "J4") (pin "DO5") (pinfunction "DO5_DO5") (pintype "bidirectional"))
      (node (ref "U3") (pin "10") (pinfunction "OUT5_10") (pintype "output"))
    )
    (net (code "95") (name "Net-(U3-OUT6)") (class "Default")
      (node (ref "J4") (pin "DO6") (pinfunction "DO6_DO6") (pintype "bidirectional"))
      (node (ref "U3") (pin "11") (pinfunction "OUT6_11") (pintype "output"))
    )
    (net (code "96") (name "Net-(U3-OUT7)") (class "Default")
      (node (ref "J4") (pin "DO7") (pinfunction "DO7_DO7") (pintype "bidirectional"))
      (node (ref "U3") (pin "12") (pinfunction "OUT7_12") (pintype "output"))
    )
    (net (code "97") (name "Net-(U3-OUT8)") (class "Default")
      (node (ref "J4") (pin "DO8") (pinfunction "DO8_DO8") (pintype "bidirectional"))
      (node (ref "U3") (pin "13") (pinfunction "OUT8_13") (pintype "output"))
    )
    (net (code "98") (name "Net-(U3-OUT9)") (class "Default")
      (node (ref "J4") (pin "DO9") (pinfunction "DO9_DO9") (pintype "bidirectional"))
      (node (ref "U3") (pin "14") (pinfunction "OUT9_14") (pintype "output"))
    )
    (net (code "99") (name "Net-(U3-OUT10)") (class "Default")
      (node (ref "J4") (pin "DO10") (pinfunction "DO10_DO10") (pintype "bidirectional"))
      (node (ref "U3") (pin "15") (pinfunction "OUT10_15") (pintype "output"))
    )
    (net (code "100") (name "Net-(U3-OUT11)") (class "Default")
      (node (ref "J4") (pin "DO11") (pinfunction "DO11_DO11") (pintype "bidirectional"))
      (node (ref "U3") (pin "16") (pinfunction "OUT11_16") (pintype "output"))
    )
    (net (code "101") (name "Net-(U3-OUT12)") (class "Default")
      (node (ref "J4") (pin "DO12") (pinfunction "DO12_DO12") (pintype "bidirectional"))
      (node (ref "U3") (pin "17") (pinfunction "OUT12_17") (pintype "output"))
    )
    (net (code "102") (name "Net-(U3-OUT13)") (class "Default")
      (node (ref "J4") (pin "DO13") (pinfunction "DO13_DO13") (pintype "bidirectional"))
      (node (ref "U3") (pin "18") (pinfunction "OUT13_18") (pintype "output"))
    )
    (net (code "103") (name "Net-(U3-OUT14)") (class "Default")
      (node (ref "J4") (pin "DO14") (pinfunction "DO14_DO14") (pintype "bidirectional"))
      (node (ref "U3") (pin "19") (pinfunction "OUT14_19") (pintype "output"))
    )
    (net (code "104") (name "Net-(U3-OUT15)") (class "Default")
      (node (ref "J4") (pin "DO15") (pinfunction "DO15_DO15") (pintype "bidirectional"))
      (node (ref "U3") (pin "20") (pinfunction "OUT15_20") (pintype "output"))
    )
    (net (code "105") (name "unconnected-(U1-(CLKO{slash}ICP3{slash}INT7)PE7-Pad9)") (class "Default")
      (node (ref "U1") (pin "9") (pinfunction "(CLKO/ICP3/INT7)PE7_9") (pintype "bidirectional"))
    )
    (net (code "106") (name "unconnected-(U1-(ICP1)PD4-Pad47)") (class "Default")
      (node (ref "U1") (pin "47") (pinfunction "(ICP1)PD4_47") (pintype "bidirectional"))
    )
    (net (code "107") (name "unconnected-(U1-(T1)PD6-Pad49)") (class "Default")
      (node (ref "U1") (pin "49") (pinfunction "(T1)PD6_49") (pintype "bidirectional"))
    )
    (net (code "108") (name "unconnected-(U1-(T3{slash}INT6)PE6-Pad8)") (class "Default")
      (node (ref "U1") (pin "8") (pinfunction "(T3/INT6)PE6_8") (pintype "bidirectional"))
    )
    (net (code "109") (name "unconnected-(U1-(TOSC1)PG4-Pad29)") (class "Default")
      (node (ref "U1") (pin "29") (pinfunction "(TOSC1)PG4_29") (pintype "bidirectional"))
    )
    (net (code "110") (name "unconnected-(U1-(TOSC2)PG3-Pad28)") (class "Default")
      (node (ref "U1") (pin "28") (pinfunction "(TOSC2)PG3_28") (pintype "bidirectional"))
    )
    (net (code "111") (name "unconnected-(U1-(XCK0{slash}AIN0)PE2-Pad4)") (class "Default")
      (node (ref "U1") (pin "4") (pinfunction "(XCK0/AIN0)PE2_4") (pintype "bidirectional"))
    )
    (net (code "112") (name "unconnected-(U1-(XCK1)PD5-Pad48)") (class "Default")
      (node (ref "U1") (pin "48") (pinfunction "(XCK1)PD5_48") (pintype "bidirectional"))
    )
    (net (code "113") (name "unconnected-(U1-PH2(XCK2)-Pad14)") (class "Default")
      (node (ref "U1") (pin "14") (pinfunction "PH2(XCK2)_14") (pintype "bidirectional"))
    )
    (net (code "114") (name "unconnected-(U1-PH7(T4)-Pad27)") (class "Default")
      (node (ref "U1") (pin "27") (pinfunction "PH7(T4)_27") (pintype "bidirectional"))
    )
    (net (code "115") (name "unconnected-(U1-PJ2(XCK3{slash}PCINT11)-Pad65)") (class "Default")
      (node (ref "U1") (pin "65") (pinfunction "PJ2(XCK3/PCINT11)_65") (pintype "bidirectional"))
    )
    (net (code "116") (name "unconnected-(U1-PJ3(PCINT12)-Pad66)") (class "Default")
      (node (ref "U1") (pin "66") (pinfunction "PJ3(PCINT12)_66") (pintype "bidirectional"))
    )
    (net (code "117") (name "unconnected-(U1-PJ4(PCINT13)-Pad67)") (class "Default")
      (node (ref "U1") (pin "67") (pinfunction "PJ4(PCINT13)_67") (pintype "bidirectional"))
    )
    (net (code "118") (name "unconnected-(U1-PJ5(PCINT14)-Pad68)") (class "Default")
      (node (ref "U1") (pin "68") (pinfunction "PJ5(PCINT14)_68") (pintype "bidirectional"))
    )
    (net (code "119") (name "unconnected-(U1-PJ6(PCINT15)-Pad69)") (class "Default")
      (node (ref "U1") (pin "69") (pinfunction "PJ6(PCINT15)_69") (pintype "bidirectional"))
    )
    (net (code "120") (name "unconnected-(U1-PJ7-Pad79)") (class "Default")
      (node (ref "U1") (pin "79") (pinfunction "PJ7_79") (pintype "bidirectional"))
    )
    (net (code "121") (name "unconnected-(U2-CTS-Pad11)") (class "Default")
      (node (ref "U2") (pin "11") (pinfunction "CTS_11") (pintype "input"))
    )
    (net (code "122") (name "unconnected-(U2-DCD-Pad10)") (class "Default")
      (node (ref "U2") (pin "10") (pinfunction "DCD_10") (pintype "input"))
    )
    (net (code "123") (name "unconnected-(U2-DSR-Pad9)") (class "Default")
      (node (ref "U2") (pin "9") (pinfunction "DSR_9") (pintype "input"))
    )
    (net (code "124") (name "unconnected-(U2-OSCI-Pad27)") (class "Default")
      (node (ref "U2") (pin "27") (pinfunction "OSCI_27") (pintype "input"))
    )
    (net (code "125") (name "unconnected-(U2-OSCO-Pad28)") (class "Default")
      (node (ref "U2") (pin "28") (pinfunction "OSCO_28") (pintype "output"))
    )
    (net (code "126") (name "unconnected-(U2-PWREN-Pad14)") (class "Default")
      (node (ref "U2") (pin "14") (pinfunction "PWREN_14") (pintype "input"))
    )
    (net (code "127") (name "unconnected-(U2-RESET-Pad19)") (class "Default")
      (node (ref "U2") (pin "19") (pinfunction "RESET_19") (pintype "input"))
    )
    (net (code "128") (name "unconnected-(U2-RI-Pad6)") (class "Default")
      (node (ref "U2") (pin "6") (pinfunction "RI_6") (pintype "input"))
    )
    (net (code "129") (name "unconnected-(U2-RTS-Pad3)") (class "Default")
      (node (ref "U2") (pin "3") (pinfunction "RTS_3") (pintype "output"))
    )
    (net (code "130") (name "unconnected-(U2-SLEEP-Pad12)") (class "Default")
      (node (ref "U2") (pin "12") (pinfunction "SLEEP_12") (pintype "input"))
    )
    (net (code "131") (name "unconnected-(U2-TXDEN-Pad13)") (class "Default")
      (node (ref "U2") (pin "13") (pinfunction "TXDEN_13") (pintype "input"))
    )
    (net (code "132") (name "unconnected-(U3-SOUT-Pad22)") (class "Default")
      (node (ref "U3") (pin "22") (pinfunction "SOUT_22") (pintype "output"))
    )
  )
)
